# USB.net
KiCad netlist of a schematic drawn in Altium Designer
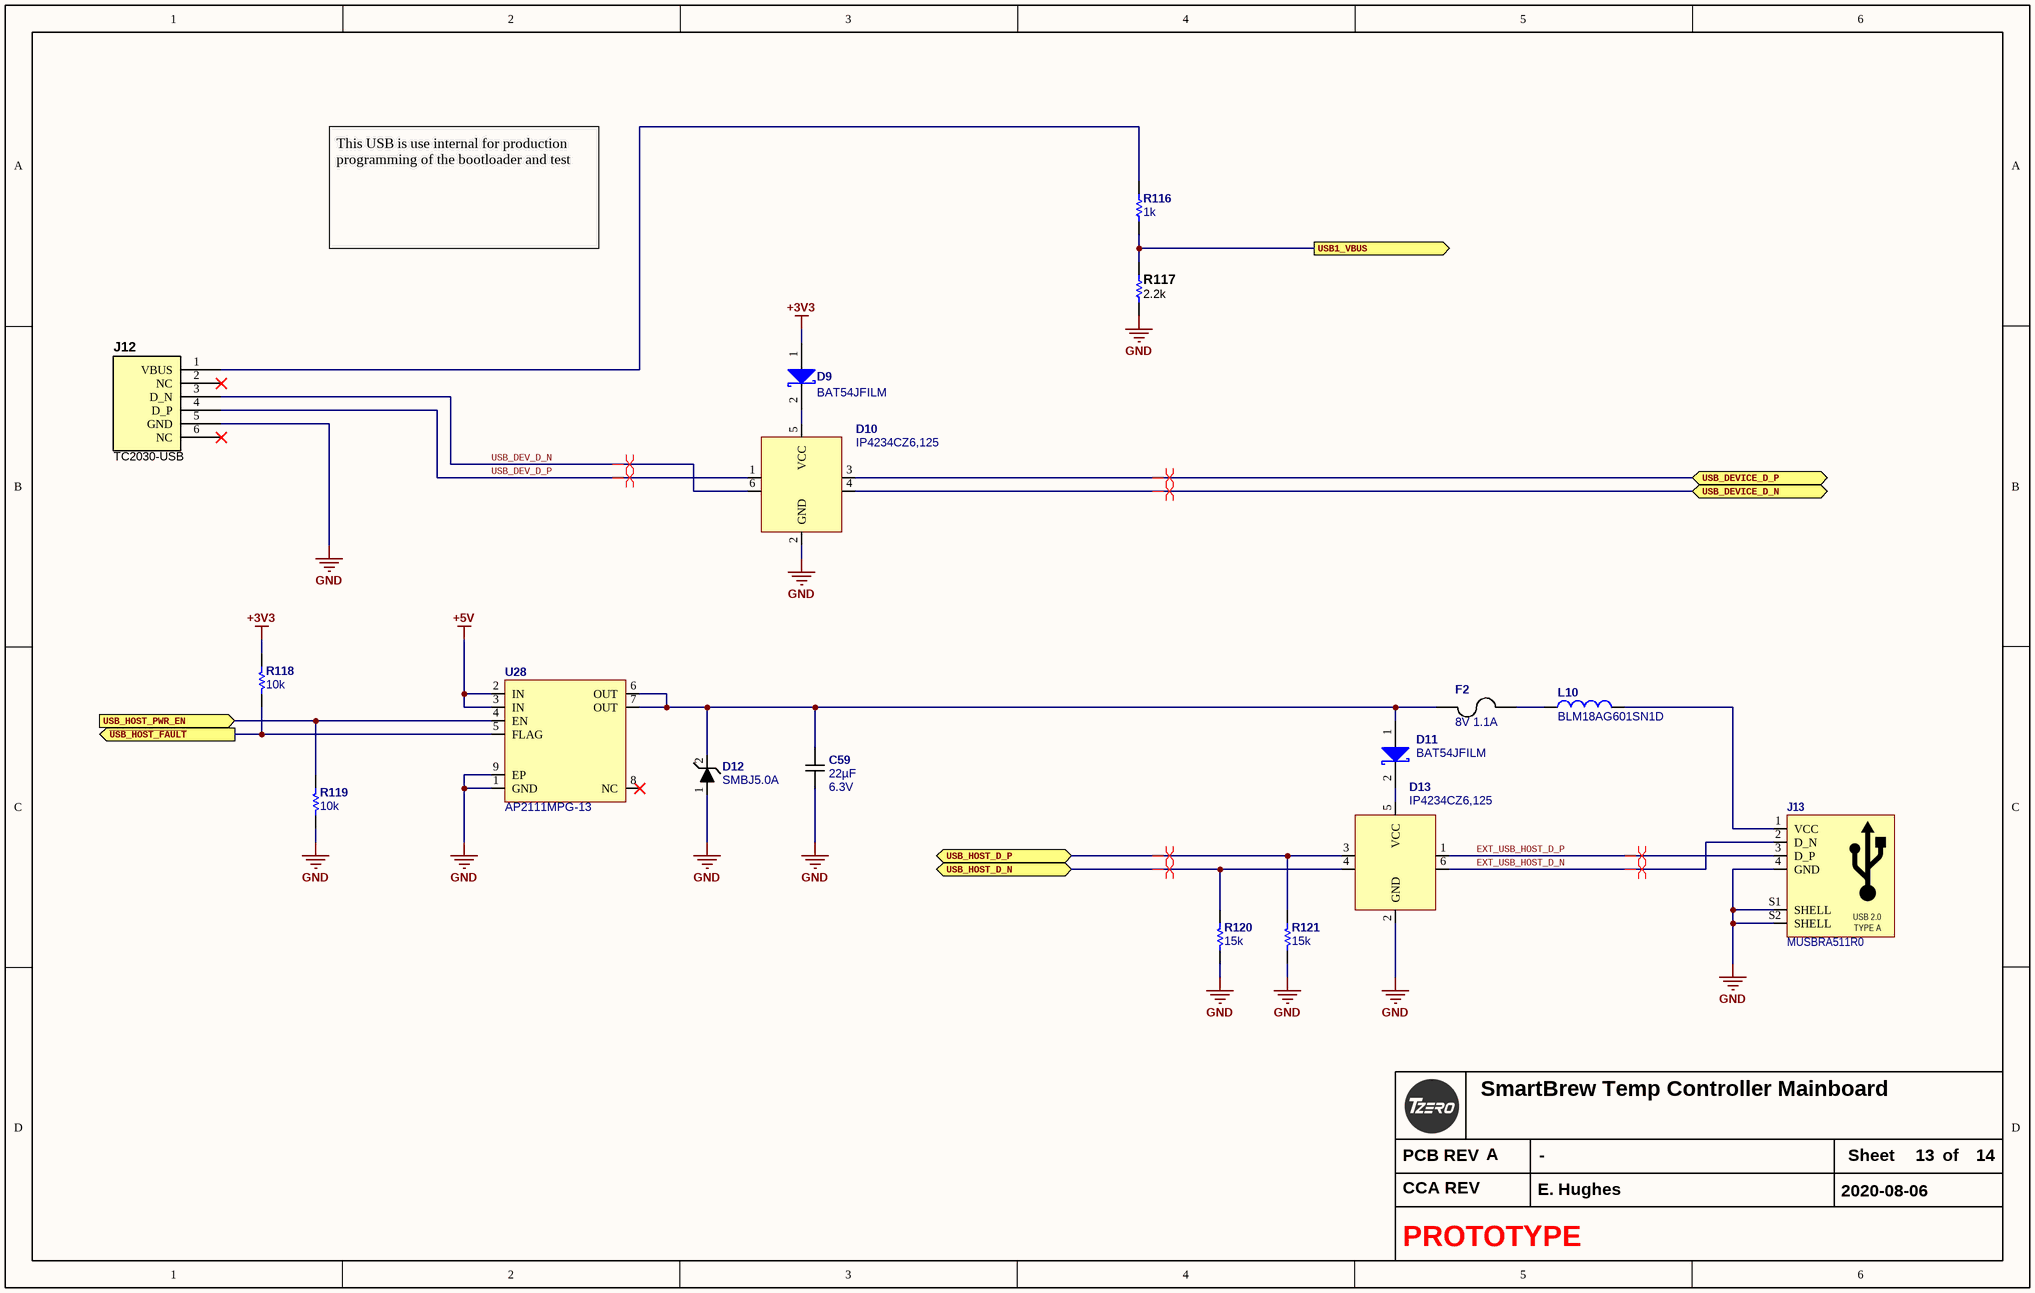
[diagram p0: USB.SchDoc]

(export (version "E")
  (design (tool "Eeschema 10.0.6"))
  (components
    (comp (ref "C59")
      (value "22µF")
      (footprint "C1206_1.60MM_HD")
      (description "CAP CER 22UF 6.3V X7R 1206")
      (fields
        (field (name "MANUFACTURER PART NUMBER") "CGA5L1X7R0J226M160AC")
        (field (name "MANUFACTURER") "TDK Corporation")
        (field (name "VOLTAGE - RATED") "6.3V")
      )
      (libsource (lib "Capacitors - TDK- AEC-Q200") (part "C_2P_NP"))
    )
    (comp (ref "D9")
      (value "BAT54JFILM")
      (footprint "SOD-323")
      (description "DIODE SCHOTTKY 40V 300MA SOD323")
      (fields (field (name "MANUFACTURER") "STMicroelectronics"))
      (libsource (lib "Diodes-N") (part "BAT54JFILM"))
    )
    (comp (ref "D10")
      (value "IP4234CZ6,125")
      (footprint "SOT427_MEDIUM")
      (description "IC USB2.0 ESD PROTECTION SOT457")
      (fields (field (name "MANUFACTURER") "NXP Semiconductors"))
      (libsource (lib "") (part "IP4234CZ6,125_1"))
    )
    (comp (ref "D11")
      (value "BAT54JFILM")
      (footprint "SOD-323")
      (description "DIODE SCHOTTKY 40V 300MA SOD323")
      (fields (field (name "MANUFACTURER") "STMicroelectronics"))
      (libsource (lib "Diodes-N") (part "BAT54JFILM"))
    )
    (comp (ref "D12")
      (value "SMBJ5.0A")
      (footprint "D_SMB_P")
      (description "TVS 5.0 VOLT 600 WATT UNI-DIR SM")
      (fields (field (name "MANUFACTURER") "Littelfuse Inc"))
      (libsource (lib "Diodes") (part "DZ_1A_2C"))
    )
    (comp (ref "D13")
      (value "IP4234CZ6,125")
      (footprint "SOT427_MEDIUM")
      (description "IC USB2.0 ESD PROTECTION SOT457")
      (fields (field (name "MANUFACTURER") "NXP Semiconductors"))
      (libsource (lib "Diodes-N") (part "IP4234CZ6,125"))
    )
    (comp (ref "F2")
      (value "8V 1.1A")
      (footprint "F_PTC_1206")
      (description "FUSE PTC RESET 8V 1.10A 1206")
      (fields
        (field (name "MANUFACTURER PART NUMBER") "1206L110THYR")
        (field (name "MANUFACTURER") "Littelfuse Inc")
      )
      (libsource (lib "Fuses") (part "F_2P"))
    )
    (comp (ref "J12")
      (value "TC2030‐USB")
      (footprint "TC2030")
      (description "Tag Connect Pads - No latching Clips - USB")
      (libsource (lib "eConnector_Debug") (part "TC2030‐USB"))
    )
    (comp (ref "J13")
      (value "MUSBRA511R0")
      (footprint "Connectors-N:AMPHENOL_MUSBR-A511")
      (description "CONN RCPT USB2.0 TYPEA 4POS PCB")
      (fields (field (name "MANUFACTURER") "Amphenol Industrial"))
      (libsource (lib "Connectors-N") (part "MUSBRA511R0"))
    )
    (comp (ref "L10")
      (value "BLM18AG601SN1D")
      (footprint "L_0603_0.8mm")
      (description "FERRITE CHIP 600 OHM 500MA 0603")
      (fields (field (name "MANUFACTURER") "Murata Electronics North America"))
      (libsource (lib "Inductors-N") (part "BLM18AG601SN1D"))
    )
    (comp (ref "R116")
      (value "1k")
      (footprint "R0603_0.55MM_MD")
      (description "RES 1K OHM 1/10W 1% 0603 SMD")
      (fields
        (field (name "MANUFACTURER PART NUMBER") "ERJ-3EKF1001V")
        (field (name "MANUFACTURER") "Panasonic Electronic Components")
      )
      (libsource (lib "Resistors - Panasonic - AEC-Q200") (part "R_2P"))
    )
    (comp (ref "R117")
      (value "2.2k")
      (footprint "R0603_0.55MM_MD")
      (description "RES 2.2K OHM 1/10W 1% 0603 SMD")
      (fields
        (field (name "MANUFACTURER PART NUMBER") "ERJ-3EKF2201V")
        (field (name "MANUFACTURER") "Panasonic Electronic Components")
      )
      (libsource (lib "Resistors - Panasonic - AEC-Q200") (part "R_2P"))
    )
    (comp (ref "R118")
      (value "10k")
      (footprint "R0603_0.55MM_MD")
      (description "RES 10K OHM 1/10W 1% 0603 SMD")
      (fields
        (field (name "MANUFACTURER") "Panasonic Electronic Components")
        (field (name "MANUFACTURER PART NUMBER") "ERJ-3EKF1002V")
      )
      (libsource (lib "Resistors - Panasonic - AEC-Q200") (part "R_2P"))
    )
    (comp (ref "R119")
      (value "10k")
      (footprint "R0603_0.55MM_MD")
      (description "RES 10K OHM 1/10W 1% 0603 SMD")
      (fields
        (field (name "MANUFACTURER") "Panasonic Electronic Components")
        (field (name "MANUFACTURER PART NUMBER") "ERJ-3EKF1002V")
      )
      (libsource (lib "Resistors - Panasonic - AEC-Q200") (part "R_2P"))
    )
    (comp (ref "R120")
      (value "15k")
      (footprint "R0603_0.55MM_MD")
      (description "RES 15K OHM 1/10W 1% 0603 SMD")
      (fields
        (field (name "MANUFACTURER") "Panasonic Electronic Components")
        (field (name "MANUFACTURER PART NUMBER") "ERJ-3EKF1502V")
      )
      (libsource (lib "Resistors - Panasonic - AEC-Q200") (part "R_2P"))
    )
    (comp (ref "R121")
      (value "15k")
      (footprint "R0603_0.55MM_MD")
      (description "RES 15K OHM 1/10W 1% 0603 SMD")
      (fields
        (field (name "MANUFACTURER") "Panasonic Electronic Components")
        (field (name "MANUFACTURER PART NUMBER") "ERJ-3EKF1502V")
      )
      (libsource (lib "Resistors - Panasonic - AEC-Q200") (part "R_2P"))
    )
    (comp (ref "U28")
      (value "AP2111MPG-13")
      (footprint "MSOP-8E")
      (description "IC USB SWITCH 2.45A CURR 8MSOP")
      (fields (field (name "MANUFACTURER") "Diodes"))
      (libsource (lib "Transistors-N") (part "AP2111MPG-13"))
    )
  )
  (nets
    (net (code "1") (name "+3V3") (class "Default")
      (node (ref "D9") (pin "1") (pinfunction "A_1") (pintype "passive"))
      (node (ref "R118") (pin "2") (pinfunction "2_2") (pintype "passive"))
    )
    (net (code "2") (name "+5V") (class "Default")
      (node (ref "U28") (pin "2") (pinfunction "IN_2") (pintype "passive"))
      (node (ref "U28") (pin "3") (pinfunction "IN_3") (pintype "passive"))
    )
    (net (code "3") (name "/EXT_USB_HOST_D_N") (class "Default")
      (node (ref "D13") (pin "6") (pinfunction "6_6") (pintype "passive"))
      (node (ref "J13") (pin "2") (pinfunction "D_N_2") (pintype "passive"))
    )
    (net (code "4") (name "/EXT_USB_HOST_D_P") (class "Default")
      (node (ref "D13") (pin "1") (pinfunction "1_1") (pintype "passive"))
      (node (ref "J13") (pin "3") (pinfunction "D_P_3") (pintype "passive"))
    )
    (net (code "5") (name "/USB1_VBUS") (class "Default")
      (node (ref "R116") (pin "2") (pinfunction "2_2") (pintype "passive"))
      (node (ref "R117") (pin "2") (pinfunction "2_2") (pintype "passive"))
    )
    (net (code "6") (name "/USB_DEVICE_D_N") (class "Default")
      (node (ref "D10") (pin "4") (pinfunction "4_4") (pintype "passive"))
    )
    (net (code "7") (name "/USB_DEVICE_D_P") (class "Default")
      (node (ref "D10") (pin "3") (pinfunction "3_3") (pintype "passive"))
    )
    (net (code "8") (name "/USB_DEV_D_N") (class "Default")
      (node (ref "D10") (pin "6") (pinfunction "6_6") (pintype "passive"))
      (node (ref "J12") (pin "3") (pinfunction "D_N_3") (pintype "passive"))
    )
    (net (code "9") (name "/USB_DEV_D_P") (class "Default")
      (node (ref "D10") (pin "1") (pinfunction "1_1") (pintype "passive"))
      (node (ref "J12") (pin "4") (pinfunction "D_P_4") (pintype "passive"))
    )
    (net (code "10") (name "/USB_HOST_D_N") (class "Default")
      (node (ref "D13") (pin "4") (pinfunction "4_4") (pintype "passive"))
      (node (ref "R120") (pin "2") (pinfunction "2_2") (pintype "passive"))
    )
    (net (code "11") (name "/USB_HOST_D_P") (class "Default")
      (node (ref "D13") (pin "3") (pinfunction "3_3") (pintype "passive"))
      (node (ref "R121") (pin "2") (pinfunction "2_2") (pintype "passive"))
    )
    (net (code "12") (name "/USB_HOST_FAULT") (class "Default")
      (node (ref "R118") (pin "1") (pinfunction "1_1") (pintype "passive"))
      (node (ref "U28") (pin "5") (pinfunction "FLAG_5") (pintype "passive"))
    )
    (net (code "13") (name "/USB_HOST_PWR_EN") (class "Default")
      (node (ref "R119") (pin "2") (pinfunction "2_2") (pintype "passive"))
      (node (ref "U28") (pin "4") (pinfunction "EN_4") (pintype "passive"))
    )
    (net (code "14") (name "GND") (class "Default")
      (node (ref "C59") (pin "1") (pinfunction "1_1") (pintype "passive"))
      (node (ref "D10") (pin "2") (pinfunction "GND_2") (pintype "passive"))
      (node (ref "D12") (pin "1") (pinfunction "A_1") (pintype "passive"))
      (node (ref "D13") (pin "2") (pinfunction "GND_2") (pintype "passive"))
      (node (ref "J12") (pin "5") (pinfunction "GND_5") (pintype "passive"))
      (node (ref "J13") (pin "4") (pinfunction "GND_4") (pintype "passive"))
      (node (ref "J13") (pin "S1") (pinfunction "SHELL_S1") (pintype "passive"))
      (node (ref "J13") (pin "S2") (pinfunction "SHELL_S2") (pintype "passive"))
      (node (ref "R117") (pin "1") (pinfunction "1_1") (pintype "passive"))
      (node (ref "R119") (pin "1") (pinfunction "1_1") (pintype "passive"))
      (node (ref "R120") (pin "1") (pinfunction "1_1") (pintype "passive"))
      (node (ref "R121") (pin "1") (pinfunction "1_1") (pintype "passive"))
      (node (ref "U28") (pin "1") (pinfunction "GND_1") (pintype "passive"))
      (node (ref "U28") (pin "9") (pinfunction "EP_9") (pintype "passive"))
    )
    (net (code "15") (name "Net-(D10-VCC)") (class "Default")
      (node (ref "D10") (pin "5") (pinfunction "VCC_5") (pintype "passive"))
      (node (ref "D9") (pin "2") (pinfunction "K_2") (pintype "passive"))
    )
    (net (code "16") (name "Net-(D11-A)") (class "Default")
      (node (ref "C59") (pin "2") (pinfunction "1_2") (pintype "passive"))
      (node (ref "D11") (pin "1") (pinfunction "A_1") (pintype "passive"))
      (node (ref "D12") (pin "2") (pinfunction "K_2") (pintype "passive"))
      (node (ref "F2") (pin "2") (pinfunction "2_2") (pintype "passive"))
      (node (ref "U28") (pin "6") (pinfunction "OUT_6") (pintype "passive"))
      (node (ref "U28") (pin "7") (pinfunction "OUT_7") (pintype "passive"))
    )
    (net (code "17") (name "Net-(D11-K)") (class "Default")
      (node (ref "D11") (pin "2") (pinfunction "K_2") (pintype "passive"))
      (node (ref "D13") (pin "5") (pinfunction "VCC_5") (pintype "passive"))
    )
    (net (code "18") (name "Net-(F2-Pad1)") (class "Default")
      (node (ref "F2") (pin "1") (pinfunction "1_1") (pintype "passive"))
      (node (ref "L10") (pin "2") (pinfunction "2_2") (pintype "passive"))
    )
    (net (code "19") (name "Net-(J12-VBUS)") (class "Default")
      (node (ref "J12") (pin "1") (pinfunction "VBUS_1") (pintype "passive"))
      (node (ref "R116") (pin "1") (pinfunction "1_1") (pintype "passive"))
    )
    (net (code "20") (name "Net-(J13-VCC)") (class "Default")
      (node (ref "J13") (pin "1") (pinfunction "VCC_1") (pintype "passive"))
      (node (ref "L10") (pin "1") (pinfunction "1_1") (pintype "passive"))
    )
    (net (code "21") (name "unconnected-(J12-NC-Pad2)") (class "Default")
      (node (ref "J12") (pin "2") (pinfunction "NC_2") (pintype "passive+no_connect"))
    )
    (net (code "22") (name "unconnected-(J12-NC-Pad6)") (class "Default")
      (node (ref "J12") (pin "6") (pinfunction "NC_6") (pintype "passive+no_connect"))
    )
    (net (code "23") (name "unconnected-(U28-NC-Pad8)") (class "Default")
      (node (ref "U28") (pin "8") (pinfunction "NC_8") (pintype "passive+no_connect"))
    )
  )
)
